# spi_node.net
KiCad netlist of a schematic drawn in EAGLE
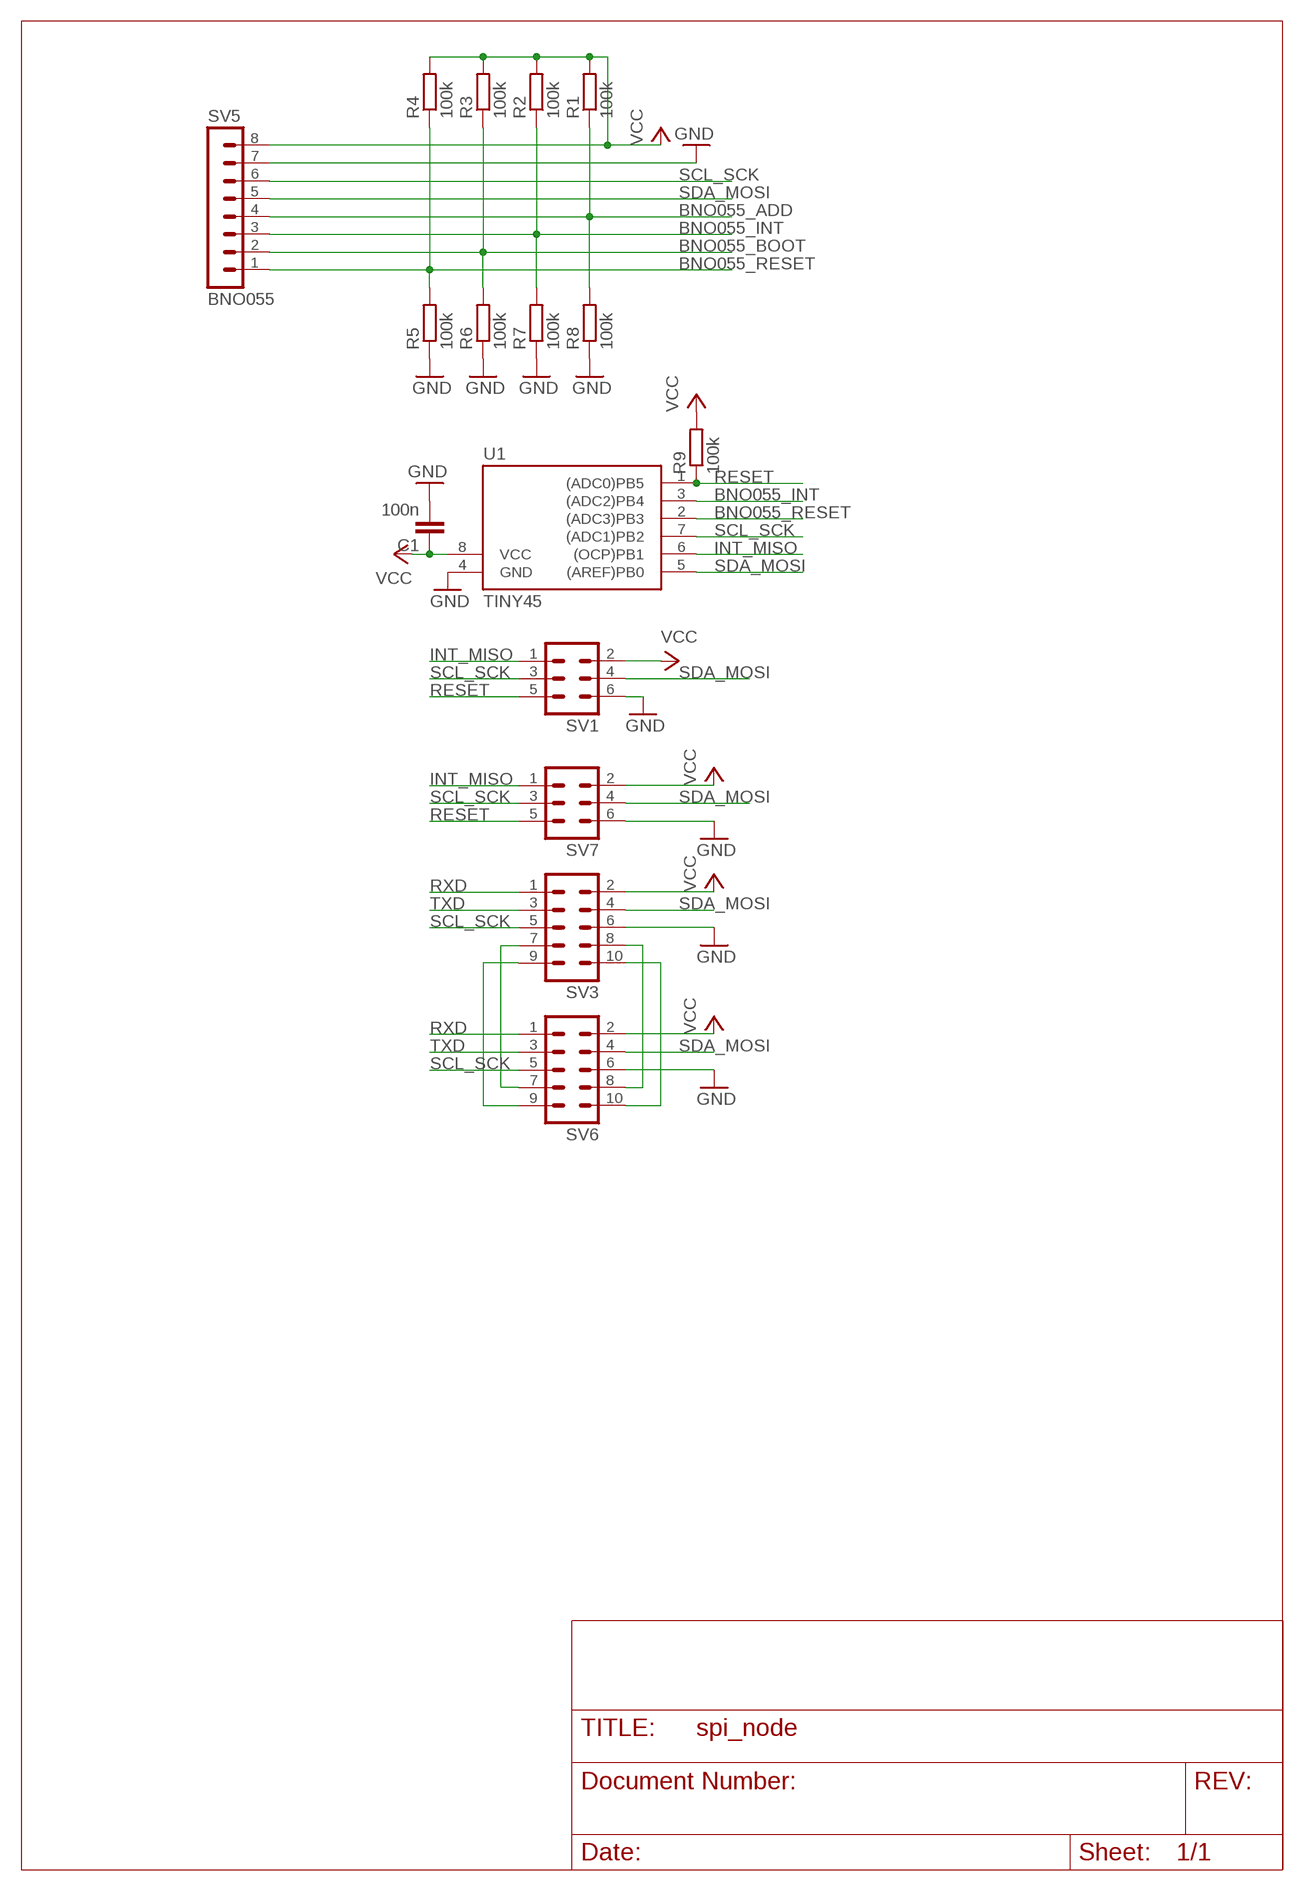
[diagram p0: schematic, sheet 1]

(export (version "E")
  (design (tool "Eeschema 10.0.6"))
  (components
    (comp (ref "C1")
      (value "100n")
      (footprint "eagle-import:C0805")
      (libsource (lib "eagle-import") (part "C-EUC0805"))
    )
    (comp (ref "R1")
      (value "100k")
      (footprint "eagle-import:M0805")
      (libsource (lib "eagle-import") (part "R-EU_M0805"))
    )
    (comp (ref "R2")
      (value "100k")
      (footprint "eagle-import:M0805")
      (libsource (lib "eagle-import") (part "R-EU_M0805"))
    )
    (comp (ref "R3")
      (value "100k")
      (footprint "eagle-import:M0805")
      (libsource (lib "eagle-import") (part "R-EU_M0805"))
    )
    (comp (ref "R4")
      (value "100k")
      (footprint "eagle-import:M0805")
      (libsource (lib "eagle-import") (part "R-EU_M0805"))
    )
    (comp (ref "R5")
      (value "100k")
      (footprint "eagle-import:M0805")
      (libsource (lib "eagle-import") (part "R-EU_M0805"))
    )
    (comp (ref "R6")
      (value "100k")
      (footprint "eagle-import:M0805")
      (libsource (lib "eagle-import") (part "R-EU_M0805"))
    )
    (comp (ref "R7")
      (value "100k")
      (footprint "eagle-import:M0805")
      (libsource (lib "eagle-import") (part "R-EU_M0805"))
    )
    (comp (ref "R8")
      (value "100k")
      (footprint "eagle-import:M0805")
      (libsource (lib "eagle-import") (part "R-EU_M0805"))
    )
    (comp (ref "R9")
      (value "100k")
      (footprint "eagle-import:M0805")
      (libsource (lib "eagle-import") (part "R-EU_M0805"))
    )
    (comp (ref "SV1")
      (value "ML6")
      (footprint "eagle-import:ML6")
      (libsource (lib "eagle-import") (part "ML6"))
    )
    (comp (ref "SV3")
      (value "ML10")
      (footprint "eagle-import:ML10")
      (libsource (lib "eagle-import") (part "ML10"))
    )
    (comp (ref "SV5")
      (value "BNO055")
      (footprint "eagle-import:MA08-1")
      (libsource (lib "eagle-import") (part "MA08-1"))
    )
    (comp (ref "SV6")
      (value "ML10")
      (footprint "eagle-import:ML10")
      (libsource (lib "eagle-import") (part "ML10"))
    )
    (comp (ref "SV7")
      (value "ML6")
      (footprint "eagle-import:ML6")
      (libsource (lib "eagle-import") (part "ML6"))
    )
    (comp (ref "U1")
      (value "TINY45")
      (footprint "eagle-import:SOIC8")
      (libsource (lib "eagle-import") (part "TINY25/45/85-20SU"))
    )
  )
  (nets
    (net (code "1") (name "/BNO055_ADD") (class "Default")
      (node (ref "R1") (pin "1") (pinfunction "1_1") (pintype "passive"))
      (node (ref "R8") (pin "2") (pinfunction "2_2") (pintype "passive"))
      (node (ref "SV5") (pin "4") (pinfunction "4_4") (pintype "passive"))
    )
    (net (code "2") (name "/BNO055_BOOT") (class "Default")
      (node (ref "R3") (pin "1") (pinfunction "1_1") (pintype "passive"))
      (node (ref "R6") (pin "2") (pinfunction "2_2") (pintype "passive"))
      (node (ref "SV5") (pin "2") (pinfunction "2_2") (pintype "passive"))
    )
    (net (code "3") (name "/BNO055_INT") (class "Default")
      (node (ref "R2") (pin "1") (pinfunction "1_1") (pintype "passive"))
      (node (ref "R7") (pin "2") (pinfunction "2_2") (pintype "passive"))
      (node (ref "SV5") (pin "3") (pinfunction "3_3") (pintype "passive"))
      (node (ref "U1") (pin "3") (pinfunction "(ADC2)PB4_3") (pintype "bidirectional"))
    )
    (net (code "4") (name "/BNO055_RESET") (class "Default")
      (node (ref "R4") (pin "1") (pinfunction "1_1") (pintype "passive"))
      (node (ref "R5") (pin "2") (pinfunction "2_2") (pintype "passive"))
      (node (ref "SV5") (pin "1") (pinfunction "1_1") (pintype "passive"))
      (node (ref "U1") (pin "2") (pinfunction "(ADC3)PB3_2") (pintype "bidirectional"))
    )
    (net (code "5") (name "/INT_MISO") (class "Default")
      (node (ref "SV1") (pin "1") (pinfunction "1_1") (pintype "passive"))
      (node (ref "SV7") (pin "1") (pinfunction "1_1") (pintype "passive"))
      (node (ref "U1") (pin "6") (pinfunction "(OCP)PB1_6") (pintype "bidirectional"))
    )
    (net (code "6") (name "/RESET") (class "Default")
      (node (ref "R9") (pin "1") (pinfunction "1_1") (pintype "passive"))
      (node (ref "SV1") (pin "5") (pinfunction "5_5") (pintype "passive"))
      (node (ref "SV7") (pin "5") (pinfunction "5_5") (pintype "passive"))
      (node (ref "U1") (pin "1") (pinfunction "(ADC0)PB5_1") (pintype "bidirectional"))
    )
    (net (code "7") (name "/RXD") (class "Default")
      (node (ref "SV3") (pin "1") (pinfunction "1_1") (pintype "passive"))
      (node (ref "SV6") (pin "1") (pinfunction "1_1") (pintype "passive"))
    )
    (net (code "8") (name "/SCL_SCK") (class "Default")
      (node (ref "SV1") (pin "3") (pinfunction "3_3") (pintype "passive"))
      (node (ref "SV3") (pin "5") (pinfunction "5_5") (pintype "passive"))
      (node (ref "SV5") (pin "6") (pinfunction "6_6") (pintype "passive"))
      (node (ref "SV6") (pin "5") (pinfunction "5_5") (pintype "passive"))
      (node (ref "SV7") (pin "3") (pinfunction "3_3") (pintype "passive"))
      (node (ref "U1") (pin "7") (pinfunction "(ADC1)PB2_7") (pintype "bidirectional"))
    )
    (net (code "9") (name "/SDA_MOSI") (class "Default")
      (node (ref "SV1") (pin "4") (pinfunction "4_4") (pintype "passive"))
      (node (ref "SV3") (pin "4") (pinfunction "4_4") (pintype "passive"))
      (node (ref "SV5") (pin "5") (pinfunction "5_5") (pintype "passive"))
      (node (ref "SV6") (pin "4") (pinfunction "4_4") (pintype "passive"))
      (node (ref "SV7") (pin "4") (pinfunction "4_4") (pintype "passive"))
      (node (ref "U1") (pin "5") (pinfunction "(AREF)PB0_5") (pintype "bidirectional"))
    )
    (net (code "10") (name "/TXD") (class "Default")
      (node (ref "SV3") (pin "3") (pinfunction "3_3") (pintype "passive"))
      (node (ref "SV6") (pin "3") (pinfunction "3_3") (pintype "passive"))
    )
    (net (code "11") (name "GND") (class "Default")
      (node (ref "C1") (pin "2") (pinfunction "2_2") (pintype "passive"))
      (node (ref "R5") (pin "1") (pinfunction "1_1") (pintype "passive"))
      (node (ref "R6") (pin "1") (pinfunction "1_1") (pintype "passive"))
      (node (ref "R7") (pin "1") (pinfunction "1_1") (pintype "passive"))
      (node (ref "R8") (pin "1") (pinfunction "1_1") (pintype "passive"))
      (node (ref "SV1") (pin "6") (pinfunction "6_6") (pintype "passive"))
      (node (ref "SV3") (pin "6") (pinfunction "6_6") (pintype "passive"))
      (node (ref "SV5") (pin "7") (pinfunction "7_7") (pintype "passive"))
      (node (ref "SV6") (pin "6") (pinfunction "6_6") (pintype "passive"))
      (node (ref "SV7") (pin "6") (pinfunction "6_6") (pintype "passive"))
      (node (ref "U1") (pin "4") (pinfunction "GND_4") (pintype "power_in"))
    )
    (net (code "12") (name "Net-(SV3-Pad7)") (class "Default")
      (node (ref "SV3") (pin "7") (pinfunction "7_7") (pintype "passive"))
      (node (ref "SV6") (pin "7") (pinfunction "7_7") (pintype "passive"))
    )
    (net (code "13") (name "Net-(SV3-Pad8)") (class "Default")
      (node (ref "SV3") (pin "8") (pinfunction "8_8") (pintype "passive"))
      (node (ref "SV6") (pin "8") (pinfunction "8_8") (pintype "passive"))
    )
    (net (code "14") (name "Net-(SV3-Pad9)") (class "Default")
      (node (ref "SV3") (pin "9") (pinfunction "9_9") (pintype "passive"))
      (node (ref "SV6") (pin "9") (pinfunction "9_9") (pintype "passive"))
    )
    (net (code "15") (name "Net-(SV3-Pad10)") (class "Default")
      (node (ref "SV3") (pin "10") (pinfunction "10_10") (pintype "passive"))
      (node (ref "SV6") (pin "10") (pinfunction "10_10") (pintype "passive"))
    )
    (net (code "16") (name "VCC") (class "Default")
      (node (ref "C1") (pin "1") (pinfunction "1_1") (pintype "passive"))
      (node (ref "R1") (pin "2") (pinfunction "2_2") (pintype "passive"))
      (node (ref "R2") (pin "2") (pinfunction "2_2") (pintype "passive"))
      (node (ref "R3") (pin "2") (pinfunction "2_2") (pintype "passive"))
      (node (ref "R4") (pin "2") (pinfunction "2_2") (pintype "passive"))
      (node (ref "R9") (pin "2") (pinfunction "2_2") (pintype "passive"))
      (node (ref "SV1") (pin "2") (pinfunction "2_2") (pintype "passive"))
      (node (ref "SV3") (pin "2") (pinfunction "2_2") (pintype "passive"))
      (node (ref "SV5") (pin "8") (pinfunction "8_8") (pintype "passive"))
      (node (ref "SV6") (pin "2") (pinfunction "2_2") (pintype "passive"))
      (node (ref "SV7") (pin "2") (pinfunction "2_2") (pintype "passive"))
      (node (ref "U1") (pin "8") (pinfunction "VCC_8") (pintype "power_in"))
    )
  )
)
